# Placa_Sensores_2019.net
KiCad netlist of a schematic drawn in EAGLE
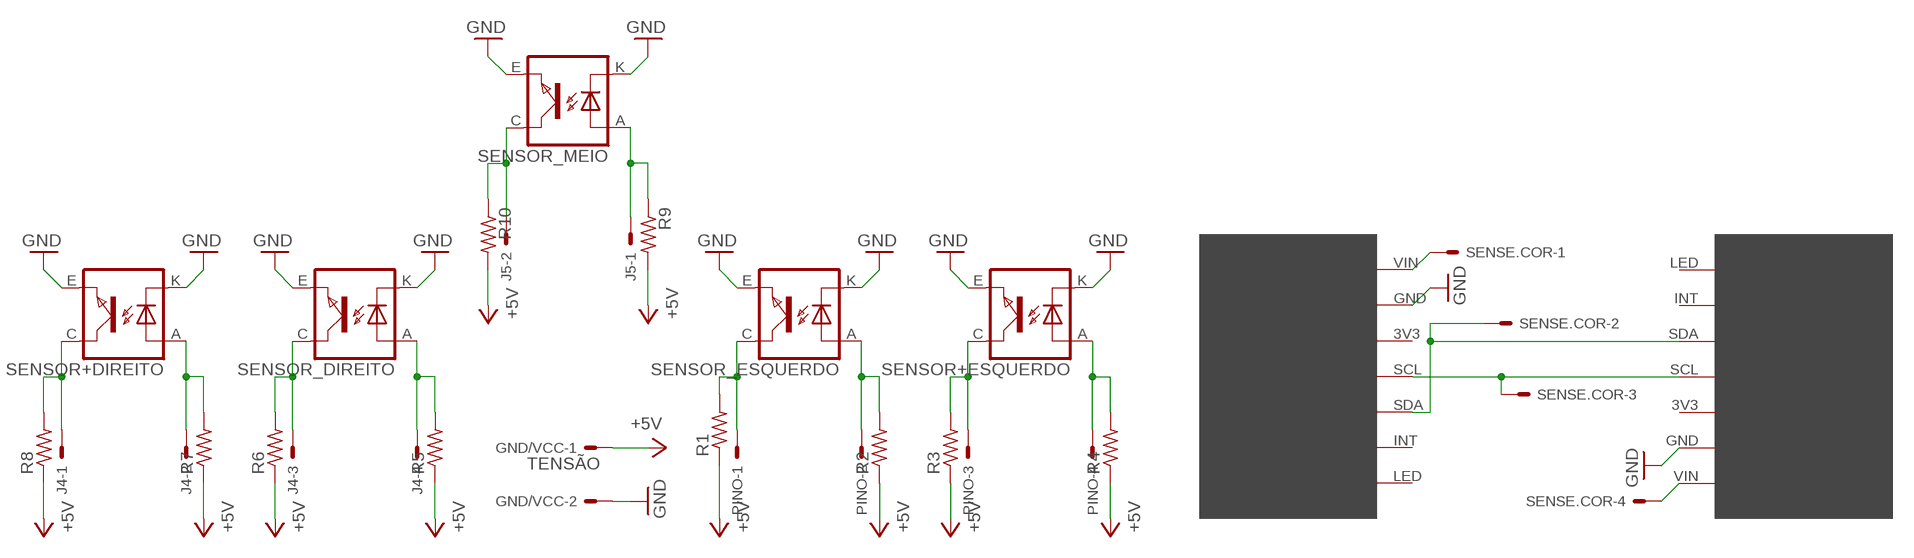
[diagram p0: schematic, sheet 1]

(export (version "E")
  (design (tool "Eeschema 10.0.6"))
  (components
    (comp (ref "GND/VCC")
      (value "TENSÃO")
      (footprint "eagle-import:6410-02")
      (libsource (lib "eagle-import") (part "CONN_0227-2021"))
    )
    (comp (ref "J4")
      (value "CONN_0427-2041")
      (footprint "eagle-import:6410-04")
      (libsource (lib "eagle-import") (part "CONN_0427-2041"))
    )
    (comp (ref "J5")
      (value "CONN_0227-2021")
      (footprint "eagle-import:6410-02")
      (libsource (lib "eagle-import") (part "CONN_0227-2021"))
    )
    (comp (ref "PINO")
      (value "CONN_0427-2041")
      (footprint "eagle-import:6410-04")
      (libsource (lib "eagle-import") (part "CONN_0427-2041"))
    )
    (comp (ref "R1")
      (value "R-US_0207/12")
      (footprint "eagle-import:0207_12")
      (libsource (lib "eagle-import") (part "R-US_0207/12"))
    )
    (comp (ref "R2")
      (value "R-US_0207/12")
      (footprint "eagle-import:0207_12")
      (libsource (lib "eagle-import") (part "R-US_0207/12"))
    )
    (comp (ref "R3")
      (value "R-US_0207/12")
      (footprint "eagle-import:0207_12")
      (libsource (lib "eagle-import") (part "R-US_0207/12"))
    )
    (comp (ref "R4")
      (value "R-US_0207/12")
      (footprint "eagle-import:0207_12")
      (libsource (lib "eagle-import") (part "R-US_0207/12"))
    )
    (comp (ref "R5")
      (value "R-US_0207/12")
      (footprint "eagle-import:0207_12")
      (libsource (lib "eagle-import") (part "R-US_0207/12"))
    )
    (comp (ref "R6")
      (value "R-US_0207/12")
      (footprint "eagle-import:0207_12")
      (libsource (lib "eagle-import") (part "R-US_0207/12"))
    )
    (comp (ref "R7")
      (value "R-US_0207/12")
      (footprint "eagle-import:0207_12")
      (libsource (lib "eagle-import") (part "R-US_0207/12"))
    )
    (comp (ref "R8")
      (value "R-US_0207/12")
      (footprint "eagle-import:0207_12")
      (libsource (lib "eagle-import") (part "R-US_0207/12"))
    )
    (comp (ref "R9")
      (value "R-US_0204/7")
      (footprint "eagle-import:0204_7")
      (libsource (lib "eagle-import") (part "R-US_0204/7"))
    )
    (comp (ref "R10")
      (value "R-US_0204/7")
      (footprint "eagle-import:0204_7")
      (libsource (lib "eagle-import") (part "R-US_0204/7"))
    )
    (comp (ref "SENSE.COR")
      (value "CONN_0427-2041")
      (footprint "eagle-import:6410-04")
      (libsource (lib "eagle-import") (part "CONN_0427-2041"))
    )
    (comp (ref "SENSOR+DIREITO")
      (value "TCRT5000")
      (footprint "eagle-import:TCRT5000")
      (libsource (lib "eagle-import") (part "TCRT5000"))
    )
    (comp (ref "SENSOR+ESQUERDO")
      (value "TCRT5000")
      (footprint "eagle-import:TCRT5000")
      (libsource (lib "eagle-import") (part "TCRT5000"))
    )
    (comp (ref "SENSOR_DIREITO")
      (value "TCRT5000")
      (footprint "eagle-import:TCRT5000")
      (libsource (lib "eagle-import") (part "TCRT5000"))
    )
    (comp (ref "SENSOR_ESQUERDO")
      (value "TCRT5000")
      (footprint "eagle-import:TCRT5000")
      (libsource (lib "eagle-import") (part "TCRT5000"))
    )
    (comp (ref "SENSOR_MEIO")
      (value "TCRT5000")
      (footprint "eagle-import:TCRT5000")
      (libsource (lib "eagle-import") (part "TCRT5000"))
    )
    (comp (ref "TCS1")
      (value "TCS34725")
      (footprint "eagle-import:TCS34725")
      (libsource (lib "eagle-import") (part "TCS34725"))
    )
    (comp (ref "TCS2")
      (value "TCS34725")
      (footprint "eagle-import:TCS34725")
      (libsource (lib "eagle-import") (part "TCS34725"))
    )
  )
  (nets
    (net (code "1") (name "+5V") (class "Default")
      (node (ref "GND/VCC") (pin "1") (pinfunction "S_1") (pintype "passive"))
      (node (ref "R1") (pin "1") (pinfunction "1_1") (pintype "passive"))
      (node (ref "R10") (pin "2") (pinfunction "2_2") (pintype "passive"))
      (node (ref "R2") (pin "1") (pinfunction "1_1") (pintype "passive"))
      (node (ref "R3") (pin "1") (pinfunction "1_1") (pintype "passive"))
      (node (ref "R4") (pin "1") (pinfunction "1_1") (pintype "passive"))
      (node (ref "R5") (pin "1") (pinfunction "1_1") (pintype "passive"))
      (node (ref "R6") (pin "1") (pinfunction "1_1") (pintype "passive"))
      (node (ref "R7") (pin "1") (pinfunction "1_1") (pintype "passive"))
      (node (ref "R8") (pin "1") (pinfunction "1_1") (pintype "passive"))
      (node (ref "R9") (pin "2") (pinfunction "2_2") (pintype "passive"))
    )
    (net (code "2") (name "GND") (class "Default")
      (node (ref "GND/VCC") (pin "2") (pinfunction "S_2") (pintype "passive"))
      (node (ref "SENSOR+DIREITO") (pin "E") (pinfunction "EMITTER_E") (pintype "passive"))
      (node (ref "SENSOR+DIREITO") (pin "K") (pinfunction "CATHODE_K") (pintype "passive"))
      (node (ref "SENSOR+ESQUERDO") (pin "E") (pinfunction "EMITTER_E") (pintype "passive"))
      (node (ref "SENSOR+ESQUERDO") (pin "K") (pinfunction "CATHODE_K") (pintype "passive"))
      (node (ref "SENSOR_DIREITO") (pin "E") (pinfunction "EMITTER_E") (pintype "passive"))
      (node (ref "SENSOR_DIREITO") (pin "K") (pinfunction "CATHODE_K") (pintype "passive"))
      (node (ref "SENSOR_ESQUERDO") (pin "E") (pinfunction "EMITTER_E") (pintype "passive"))
      (node (ref "SENSOR_ESQUERDO") (pin "K") (pinfunction "CATHODE_K") (pintype "passive"))
      (node (ref "SENSOR_MEIO") (pin "E") (pinfunction "EMITTER_E") (pintype "passive"))
      (node (ref "SENSOR_MEIO") (pin "K") (pinfunction "CATHODE_K") (pintype "passive"))
      (node (ref "TCS1") (pin "GND") (pinfunction "GND_GND") (pintype "bidirectional"))
      (node (ref "TCS2") (pin "GND") (pinfunction "GND_GND") (pintype "bidirectional"))
    )
    (net (code "3") (name "Net-(J4A-S)") (class "Default")
      (node (ref "J4") (pin "1") (pinfunction "S_1") (pintype "passive"))
      (node (ref "R8") (pin "2") (pinfunction "2_2") (pintype "passive"))
      (node (ref "SENSOR+DIREITO") (pin "C") (pinfunction "COLLECTOR_C") (pintype "passive"))
    )
    (net (code "4") (name "Net-(J4B-S)") (class "Default")
      (node (ref "J4") (pin "2") (pinfunction "S_2") (pintype "passive"))
      (node (ref "R7") (pin "2") (pinfunction "2_2") (pintype "passive"))
      (node (ref "SENSOR+DIREITO") (pin "A") (pinfunction "ANODE_A") (pintype "passive"))
    )
    (net (code "5") (name "Net-(J4C-S)") (class "Default")
      (node (ref "J4") (pin "3") (pinfunction "S_3") (pintype "passive"))
      (node (ref "R6") (pin "2") (pinfunction "2_2") (pintype "passive"))
      (node (ref "SENSOR_DIREITO") (pin "C") (pinfunction "COLLECTOR_C") (pintype "passive"))
    )
    (net (code "6") (name "Net-(J4D-S)") (class "Default")
      (node (ref "J4") (pin "4") (pinfunction "S_4") (pintype "passive"))
      (node (ref "R5") (pin "2") (pinfunction "2_2") (pintype "passive"))
      (node (ref "SENSOR_DIREITO") (pin "A") (pinfunction "ANODE_A") (pintype "passive"))
    )
    (net (code "7") (name "Net-(J5A-S)") (class "Default")
      (node (ref "J5") (pin "1") (pinfunction "S_1") (pintype "passive"))
      (node (ref "R9") (pin "1") (pinfunction "1_1") (pintype "passive"))
      (node (ref "SENSOR_MEIO") (pin "A") (pinfunction "ANODE_A") (pintype "passive"))
    )
    (net (code "8") (name "Net-(J5B-S)") (class "Default")
      (node (ref "J5") (pin "2") (pinfunction "S_2") (pintype "passive"))
      (node (ref "R10") (pin "1") (pinfunction "1_1") (pintype "passive"))
      (node (ref "SENSOR_MEIO") (pin "C") (pinfunction "COLLECTOR_C") (pintype "passive"))
    )
    (net (code "9") (name "Net-(PINOA-S)") (class "Default")
      (node (ref "PINO") (pin "1") (pinfunction "S_1") (pintype "passive"))
      (node (ref "R1") (pin "2") (pinfunction "2_2") (pintype "passive"))
      (node (ref "SENSOR_ESQUERDO") (pin "C") (pinfunction "COLLECTOR_C") (pintype "passive"))
    )
    (net (code "10") (name "Net-(PINOB-S)") (class "Default")
      (node (ref "PINO") (pin "2") (pinfunction "S_2") (pintype "passive"))
      (node (ref "R2") (pin "2") (pinfunction "2_2") (pintype "passive"))
      (node (ref "SENSOR_ESQUERDO") (pin "A") (pinfunction "ANODE_A") (pintype "passive"))
    )
    (net (code "11") (name "Net-(PINOC-S)") (class "Default")
      (node (ref "PINO") (pin "3") (pinfunction "S_3") (pintype "passive"))
      (node (ref "R3") (pin "2") (pinfunction "2_2") (pintype "passive"))
      (node (ref "SENSOR+ESQUERDO") (pin "C") (pinfunction "COLLECTOR_C") (pintype "passive"))
    )
    (net (code "12") (name "Net-(PINOD-S)") (class "Default")
      (node (ref "PINO") (pin "4") (pinfunction "S_4") (pintype "passive"))
      (node (ref "R4") (pin "2") (pinfunction "2_2") (pintype "passive"))
      (node (ref "SENSOR+ESQUERDO") (pin "A") (pinfunction "ANODE_A") (pintype "passive"))
    )
    (net (code "13") (name "Net-(SENSE.CORA-S)") (class "Default")
      (node (ref "SENSE.COR") (pin "1") (pinfunction "S_1") (pintype "passive"))
      (node (ref "TCS1") (pin "VIN") (pinfunction "VIN_VIN") (pintype "bidirectional"))
    )
    (net (code "14") (name "Net-(SENSE.CORB-S)") (class "Default")
      (node (ref "SENSE.COR") (pin "2") (pinfunction "S_2") (pintype "passive"))
      (node (ref "TCS1") (pin "SDA") (pinfunction "SDA_SDA") (pintype "bidirectional"))
      (node (ref "TCS2") (pin "SDA") (pinfunction "SDA_SDA") (pintype "bidirectional"))
    )
    (net (code "15") (name "Net-(SENSE.CORC-S)") (class "Default")
      (node (ref "SENSE.COR") (pin "3") (pinfunction "S_3") (pintype "passive"))
      (node (ref "TCS1") (pin "SCL") (pinfunction "SCL_SCL") (pintype "bidirectional"))
      (node (ref "TCS2") (pin "SCL") (pinfunction "SCL_SCL") (pintype "bidirectional"))
    )
    (net (code "16") (name "Net-(SENSE.CORD-S)") (class "Default")
      (node (ref "SENSE.COR") (pin "4") (pinfunction "S_4") (pintype "passive"))
      (node (ref "TCS2") (pin "VIN") (pinfunction "VIN_VIN") (pintype "bidirectional"))
    )
    (net (code "17") (name "unconnected-(TCS1-Pad3V3)") (class "Default")
      (node (ref "TCS1") (pin "3V3") (pinfunction "3V3_3V3") (pintype "bidirectional"))
    )
    (net (code "18") (name "unconnected-(TCS1-PadINT)") (class "Default")
      (node (ref "TCS1") (pin "INT") (pinfunction "INT_INT") (pintype "bidirectional"))
    )
    (net (code "19") (name "unconnected-(TCS1-PadLED)") (class "Default")
      (node (ref "TCS1") (pin "LED") (pinfunction "LED_LED") (pintype "bidirectional"))
    )
    (net (code "20") (name "unconnected-(TCS2-Pad3V3)") (class "Default")
      (node (ref "TCS2") (pin "3V3") (pinfunction "3V3_3V3") (pintype "bidirectional"))
    )
    (net (code "21") (name "unconnected-(TCS2-PadINT)") (class "Default")
      (node (ref "TCS2") (pin "INT") (pinfunction "INT_INT") (pintype "bidirectional"))
    )
    (net (code "22") (name "unconnected-(TCS2-PadLED)") (class "Default")
      (node (ref "TCS2") (pin "LED") (pinfunction "LED_LED") (pintype "bidirectional"))
    )
  )
)
